# BMS_TEMP.net
KiCad netlist of a schematic drawn in Altium Designer
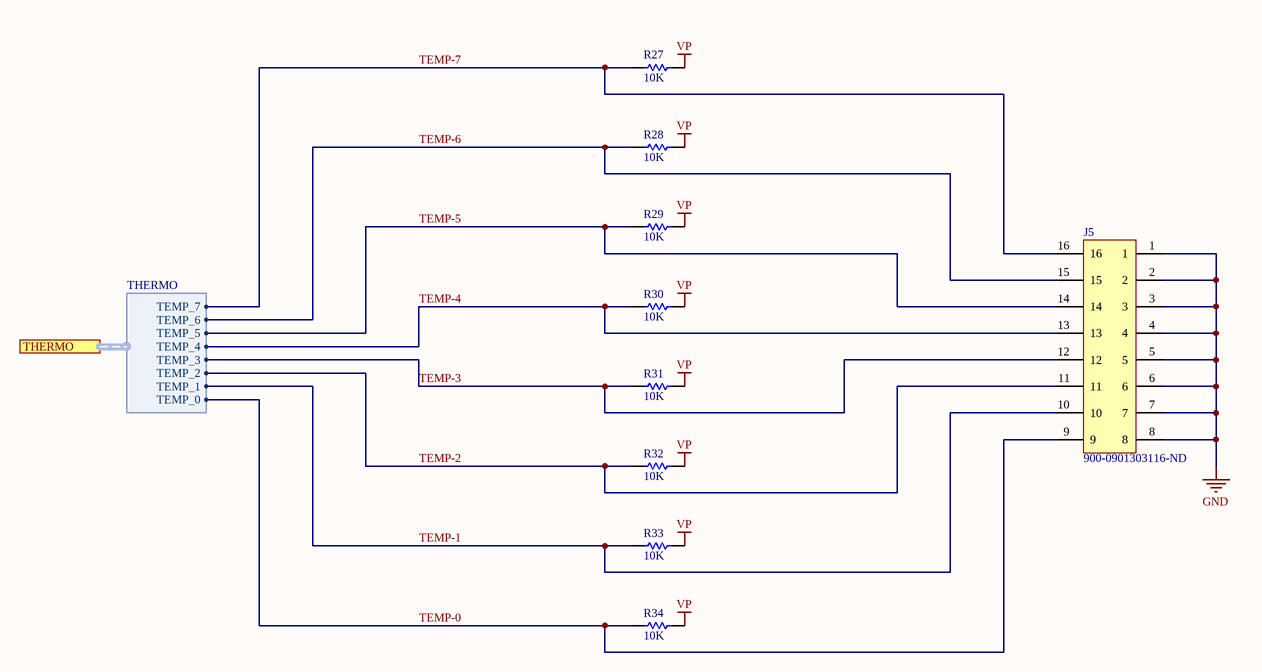
[diagram p0: BMS_TEMP.SchDoc]

(export (version "E")
  (design (tool "Eeschema 10.0.6"))
  (components
    (comp (ref "J5")
      (value "900-0901303116-ND")
      (footprint "2X8PIN")
      (description "CONN HEADER R/A 16POS 2.54MM")
      (fields (field (name "MANUFACTURER") "Molex") (field (name "MANUFACTURER PART NUMBER") "90130-3116"))
      (libsource (lib "Connectors") (part "2X8PIN"))
    )
    (comp (ref "R27")
      (value "10K")
      (footprint "RES-0603")
      (description "RES SMD 10K OHM 5% 1/10W 0603")
      (fields
        (field (name "MANUFACTURER") "Yageo")
        (field (name "MANUFACTURER PART NUMBER") "RC0603JR-0710KL")
      )
      (libsource (lib "Resistors") (part "0603-10KR"))
    )
    (comp (ref "R28")
      (value "10K")
      (footprint "RES-0603")
      (description "RES SMD 10K OHM 5% 1/10W 0603")
      (fields
        (field (name "MANUFACTURER") "Yageo")
        (field (name "MANUFACTURER PART NUMBER") "RC0603JR-0710KL")
      )
      (libsource (lib "Resistors") (part "0603-10KR"))
    )
    (comp (ref "R29")
      (value "10K")
      (footprint "RES-0603")
      (description "RES SMD 10K OHM 5% 1/10W 0603")
      (fields
        (field (name "MANUFACTURER") "Yageo")
        (field (name "MANUFACTURER PART NUMBER") "RC0603JR-0710KL")
      )
      (libsource (lib "Resistors") (part "0603-10KR"))
    )
    (comp (ref "R30")
      (value "10K")
      (footprint "RES-0603")
      (description "RES SMD 10K OHM 5% 1/10W 0603")
      (fields
        (field (name "MANUFACTURER") "Yageo")
        (field (name "MANUFACTURER PART NUMBER") "RC0603JR-0710KL")
      )
      (libsource (lib "Resistors") (part "0603-10KR"))
    )
    (comp (ref "R31")
      (value "10K")
      (footprint "RES-0603")
      (description "RES SMD 10K OHM 5% 1/10W 0603")
      (fields
        (field (name "MANUFACTURER") "Yageo")
        (field (name "MANUFACTURER PART NUMBER") "RC0603JR-0710KL")
      )
      (libsource (lib "Resistors") (part "0603-10KR"))
    )
    (comp (ref "R32")
      (value "10K")
      (footprint "RES-0603")
      (description "RES SMD 10K OHM 5% 1/10W 0603")
      (fields
        (field (name "MANUFACTURER") "Yageo")
        (field (name "MANUFACTURER PART NUMBER") "RC0603JR-0710KL")
      )
      (libsource (lib "Resistors") (part "0603-10KR"))
    )
    (comp (ref "R33")
      (value "10K")
      (footprint "RES-0603")
      (description "RES SMD 10K OHM 5% 1/10W 0603")
      (fields
        (field (name "MANUFACTURER") "Yageo")
        (field (name "MANUFACTURER PART NUMBER") "RC0603JR-0710KL")
      )
      (libsource (lib "Resistors") (part "0603-10KR"))
    )
    (comp (ref "R34")
      (value "10K")
      (footprint "RES-0603")
      (description "RES SMD 10K OHM 5% 1/10W 0603")
      (fields
        (field (name "MANUFACTURER") "Yageo")
        (field (name "MANUFACTURER PART NUMBER") "RC0603JR-0710KL")
      )
      (libsource (lib "Resistors") (part "0603-10KR"))
    )
  )
  (nets
    (net (code "2") (name "/TEMP-0") (class "Default")
      (node (ref "J5") (pin "9") (pinfunction "9_9") (pintype "passive"))
      (node (ref "R34") (pin "2") (pinfunction "2_2") (pintype "passive"))
    )
    (net (code "3") (name "/TEMP-1") (class "Default")
      (node (ref "J5") (pin "10") (pinfunction "10_10") (pintype "passive"))
      (node (ref "R33") (pin "2") (pinfunction "2_2") (pintype "passive"))
    )
    (net (code "4") (name "/TEMP-2") (class "Default")
      (node (ref "J5") (pin "11") (pinfunction "11_11") (pintype "passive"))
      (node (ref "R32") (pin "2") (pinfunction "2_2") (pintype "passive"))
    )
    (net (code "5") (name "/TEMP-3") (class "Default")
      (node (ref "J5") (pin "12") (pinfunction "12_12") (pintype "passive"))
      (node (ref "R31") (pin "2") (pinfunction "2_2") (pintype "passive"))
    )
    (net (code "6") (name "/TEMP-4") (class "Default")
      (node (ref "J5") (pin "13") (pinfunction "13_13") (pintype "passive"))
      (node (ref "R30") (pin "2") (pinfunction "2_2") (pintype "passive"))
    )
    (net (code "7") (name "/TEMP-5") (class "Default")
      (node (ref "J5") (pin "14") (pinfunction "14_14") (pintype "passive"))
      (node (ref "R29") (pin "2") (pinfunction "2_2") (pintype "passive"))
    )
    (net (code "8") (name "/TEMP-6") (class "Default")
      (node (ref "J5") (pin "15") (pinfunction "15_15") (pintype "passive"))
      (node (ref "R28") (pin "2") (pinfunction "2_2") (pintype "passive"))
    )
    (net (code "9") (name "/TEMP-7") (class "Default")
      (node (ref "J5") (pin "16") (pinfunction "16_16") (pintype "passive"))
      (node (ref "R27") (pin "2") (pinfunction "2_2") (pintype "passive"))
    )
    (net (code "11") (name "GND") (class "Default")
      (node (ref "J5") (pin "1") (pinfunction "1_1") (pintype "passive"))
      (node (ref "J5") (pin "2") (pinfunction "2_2") (pintype "passive"))
      (node (ref "J5") (pin "3") (pinfunction "3_3") (pintype "passive"))
      (node (ref "J5") (pin "4") (pinfunction "4_4") (pintype "passive"))
      (node (ref "J5") (pin "5") (pinfunction "5_5") (pintype "passive"))
      (node (ref "J5") (pin "6") (pinfunction "6_6") (pintype "passive"))
      (node (ref "J5") (pin "7") (pinfunction "7_7") (pintype "passive"))
      (node (ref "J5") (pin "8") (pinfunction "8_8") (pintype "passive"))
    )
    (net (code "12") (name "VP") (class "Default")
      (node (ref "R27") (pin "1") (pinfunction "1_1") (pintype "passive"))
      (node (ref "R28") (pin "1") (pinfunction "1_1") (pintype "passive"))
      (node (ref "R29") (pin "1") (pinfunction "1_1") (pintype "passive"))
      (node (ref "R30") (pin "1") (pinfunction "1_1") (pintype "passive"))
      (node (ref "R31") (pin "1") (pinfunction "1_1") (pintype "passive"))
      (node (ref "R32") (pin "1") (pinfunction "1_1") (pintype "passive"))
      (node (ref "R33") (pin "1") (pinfunction "1_1") (pintype "passive"))
      (node (ref "R34") (pin "1") (pinfunction "1_1") (pintype "passive"))
    )
  )
)
